# brush.net
KiCad netlist of a schematic drawn in EAGLE
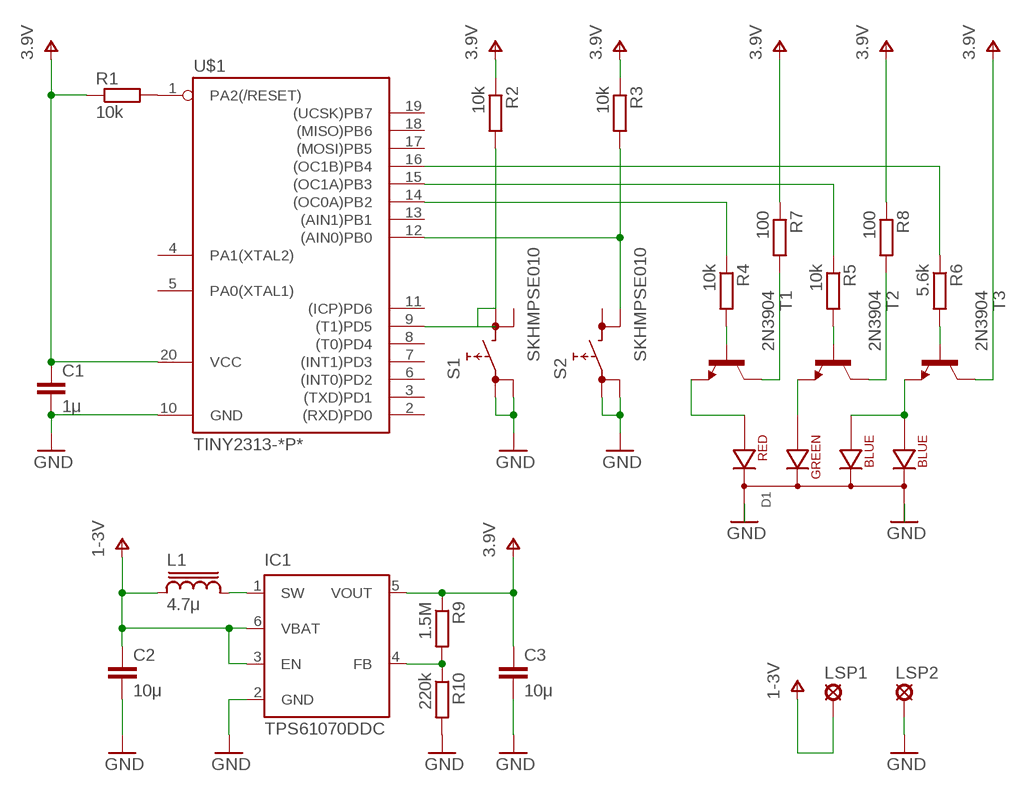
[diagram p0: schematic, sheet 1]

(export (version "E")
  (design (tool "Eeschema 10.0.6"))
  (components
    (comp (ref "C1")
      (value "1μ")
      (footprint "eagle-import:C1206")
      (libsource (lib "eagle-import") (part "C-EUC1206"))
    )
    (comp (ref "C2")
      (value "10μ")
      (footprint "eagle-import:C1206")
      (libsource (lib "eagle-import") (part "C-EUC1206"))
    )
    (comp (ref "C3")
      (value "10μ")
      (footprint "eagle-import:C1206")
      (libsource (lib "eagle-import") (part "C-EUC1206"))
    )
    (comp (ref "D1")
      (value "LED-RGB-CC-THRUDIFFUSE")
      (footprint "eagle-import:LED-RGB-THRU")
      (libsource (lib "eagle-import") (part "LED-RGB-CC-THRUDIFFUSE"))
    )
    (comp (ref "IC1")
      (value "TPS61070DDC")
      (footprint "eagle-import:TSOT23-6_DDC")
      (fields (field (name "MPN") "TPS61070DDCR"))
      (libsource (lib "eagle-import") (part "TPS6107DDC0"))
    )
    (comp (ref "L1")
      (value "4.7μ")
      (footprint "eagle-import:CR43")
      (libsource (lib "eagle-import") (part "CR43"))
    )
    (comp (ref "LSP1")
      (value "LSP10")
      (footprint "eagle-import:LSP10")
      (libsource (lib "eagle-import") (part "LSP10"))
    )
    (comp (ref "LSP2")
      (value "LSP10")
      (footprint "eagle-import:LSP10")
      (libsource (lib "eagle-import") (part "LSP10"))
    )
    (comp (ref "R1")
      (value "10k")
      (footprint "eagle-import:R1206")
      (libsource (lib "eagle-import") (part "R-EU_R1206"))
    )
    (comp (ref "R2")
      (value "10k")
      (footprint "eagle-import:R1206")
      (libsource (lib "eagle-import") (part "R-EU_R1206"))
    )
    (comp (ref "R3")
      (value "10k")
      (footprint "eagle-import:R1206")
      (libsource (lib "eagle-import") (part "R-EU_R1206"))
    )
    (comp (ref "R4")
      (value "10k")
      (footprint "eagle-import:R1206")
      (libsource (lib "eagle-import") (part "R-EU_R1206"))
    )
    (comp (ref "R5")
      (value "10k")
      (footprint "eagle-import:R1206")
      (libsource (lib "eagle-import") (part "R-EU_R1206"))
    )
    (comp (ref "R6")
      (value "5.6k")
      (footprint "eagle-import:R1206")
      (libsource (lib "eagle-import") (part "R-EU_R1206"))
    )
    (comp (ref "R7")
      (value "100")
      (footprint "eagle-import:R1206")
      (libsource (lib "eagle-import") (part "R-EU_R1206"))
    )
    (comp (ref "R8")
      (value "100")
      (footprint "eagle-import:R1206")
      (libsource (lib "eagle-import") (part "R-EU_R1206"))
    )
    (comp (ref "R9")
      (value "1.5M")
      (footprint "eagle-import:R1206")
      (libsource (lib "eagle-import") (part "R-EU_R1206"))
    )
    (comp (ref "R10")
      (value "220k")
      (footprint "eagle-import:R1206")
      (libsource (lib "eagle-import") (part "R-EU_R1206"))
    )
    (comp (ref "S1")
      (value "SKHMPSE010")
      (footprint "eagle-import:SKHMPXE010")
      (libsource (lib "eagle-import") (part "SKHMPE010S"))
    )
    (comp (ref "S2")
      (value "SKHMPSE010")
      (footprint "eagle-import:SKHMPXE010")
      (libsource (lib "eagle-import") (part "SKHMPE010S"))
    )
    (comp (ref "T1")
      (value "2N3904")
      (footprint "eagle-import:TO92")
      (libsource (lib "eagle-import") (part "2N3904"))
    )
    (comp (ref "T2")
      (value "2N3904")
      (footprint "eagle-import:TO92")
      (libsource (lib "eagle-import") (part "2N3904"))
    )
    (comp (ref "T3")
      (value "2N3904")
      (footprint "eagle-import:TO92")
      (libsource (lib "eagle-import") (part "2N3904"))
    )
    (comp (ref "U$1")
      (value "TINY2313-*P*")
      (footprint "eagle-import:DIL20")
      (libsource (lib "eagle-import") (part "TINY2313-P"))
    )
  )
  (nets
    (net (code "1") (name "1-3V") (class "Default")
      (node (ref "C1") (pin "1") (pinfunction "1_1") (pintype "passive"))
      (node (ref "C2") (pin "1") (pinfunction "1_1") (pintype "passive"))
      (node (ref "C3") (pin "1") (pinfunction "1_1") (pintype "passive"))
      (node (ref "IC1") (pin "3") (pinfunction "EN_3") (pintype "input"))
      (node (ref "IC1") (pin "5") (pinfunction "VOUT_5") (pintype "passive"))
      (node (ref "IC1") (pin "6") (pinfunction "VBAT_6") (pintype "input"))
      (node (ref "L1") (pin "1") (pinfunction "1_1") (pintype "passive"))
      (node (ref "LSP1") (pin "MP") (pinfunction "MP_MP") (pintype "passive"))
      (node (ref "R1") (pin "1") (pinfunction "1_1") (pintype "passive"))
      (node (ref "R2") (pin "1") (pinfunction "1_1") (pintype "passive"))
      (node (ref "R3") (pin "1") (pinfunction "1_1") (pintype "passive"))
      (node (ref "R7") (pin "1") (pinfunction "1_1") (pintype "passive"))
      (node (ref "R8") (pin "1") (pinfunction "1_1") (pintype "passive"))
      (node (ref "R9") (pin "1") (pinfunction "1_1") (pintype "passive"))
      (node (ref "T3") (pin "1") (pinfunction "C_1") (pintype "passive"))
      (node (ref "U$1") (pin "20") (pinfunction "VCC_20") (pintype "power_in"))
    )
    (net (code "2") (name "GND") (class "Default")
      (node (ref "C1") (pin "2") (pinfunction "2_2") (pintype "passive"))
      (node (ref "C2") (pin "2") (pinfunction "2_2") (pintype "passive"))
      (node (ref "C3") (pin "2") (pinfunction "2_2") (pintype "passive"))
      (node (ref "D1") (pin "CATHODE1") (pinfunction "CATHODE1_CATHODE1") (pintype "bidirectional"))
      (node (ref "D1") (pin "CATHODE2") (pinfunction "CATHODE2_CATHODE2") (pintype "bidirectional"))
      (node (ref "IC1") (pin "2") (pinfunction "GND_2") (pintype "power_in"))
      (node (ref "LSP2") (pin "MP") (pinfunction "MP_MP") (pintype "passive"))
      (node (ref "R10") (pin "2") (pinfunction "2_2") (pintype "passive"))
      (node (ref "S1") (pin "1") (pinfunction "1.1_1") (pintype "passive"))
      (node (ref "S1") (pin "2") (pinfunction "1.2_2") (pintype "passive"))
      (node (ref "S2") (pin "1") (pinfunction "1.1_1") (pintype "passive"))
      (node (ref "S2") (pin "2") (pinfunction "1.2_2") (pintype "passive"))
      (node (ref "U$1") (pin "10") (pinfunction "GND_10") (pintype "power_in"))
    )
    (net (code "3") (name "Net-(IC1-FB)") (class "Default")
      (node (ref "IC1") (pin "4") (pinfunction "FB_4") (pintype "input"))
      (node (ref "R10") (pin "1") (pinfunction "1_1") (pintype "passive"))
      (node (ref "R9") (pin "2") (pinfunction "2_2") (pintype "passive"))
    )
    (net (code "4") (name "Net-(IC1-SW)") (class "Default")
      (node (ref "IC1") (pin "1") (pinfunction "SW_1") (pintype "input"))
      (node (ref "L1") (pin "2") (pinfunction "2_2") (pintype "passive"))
    )
    (net (code "5") (name "Net-(S1-2.1)") (class "Default")
      (node (ref "R2") (pin "2") (pinfunction "2_2") (pintype "passive"))
      (node (ref "S1") (pin "3") (pinfunction "2.1_3") (pintype "passive"))
      (node (ref "U$1") (pin "9") (pinfunction "(T1)PD5_9") (pintype "bidirectional"))
    )
    (net (code "6") (name "Net-(S2-2.2)") (class "Default")
      (node (ref "R3") (pin "2") (pinfunction "2_2") (pintype "passive"))
      (node (ref "S2") (pin "4") (pinfunction "2.2_4") (pintype "passive"))
      (node (ref "U$1") (pin "12") (pinfunction "(AIN0)PB0_12") (pintype "bidirectional"))
    )
    (net (code "7") (name "Net-(T1-B)") (class "Default")
      (node (ref "R4") (pin "2") (pinfunction "2_2") (pintype "passive"))
      (node (ref "T1") (pin "2") (pinfunction "B_2") (pintype "passive"))
    )
    (net (code "8") (name "Net-(T1-C)") (class "Default")
      (node (ref "R7") (pin "2") (pinfunction "2_2") (pintype "passive"))
      (node (ref "T1") (pin "1") (pinfunction "C_1") (pintype "passive"))
    )
    (net (code "9") (name "Net-(T1-E)") (class "Default")
      (node (ref "D1") (pin "RED") (pinfunction "RED_RED") (pintype "bidirectional"))
      (node (ref "T1") (pin "3") (pinfunction "E_3") (pintype "passive"))
    )
    (net (code "10") (name "Net-(T2-B)") (class "Default")
      (node (ref "R5") (pin "2") (pinfunction "2_2") (pintype "passive"))
      (node (ref "T2") (pin "2") (pinfunction "B_2") (pintype "passive"))
    )
    (net (code "11") (name "Net-(T2-C)") (class "Default")
      (node (ref "R8") (pin "2") (pinfunction "2_2") (pintype "passive"))
      (node (ref "T2") (pin "1") (pinfunction "C_1") (pintype "passive"))
    )
    (net (code "12") (name "Net-(T2-E)") (class "Default")
      (node (ref "D1") (pin "GREEN") (pinfunction "GREEN_GREEN") (pintype "bidirectional"))
      (node (ref "T2") (pin "3") (pinfunction "E_3") (pintype "passive"))
    )
    (net (code "13") (name "Net-(T3-B)") (class "Default")
      (node (ref "R6") (pin "2") (pinfunction "2_2") (pintype "passive"))
      (node (ref "T3") (pin "2") (pinfunction "B_2") (pintype "passive"))
    )
    (net (code "14") (name "Net-(T3-E)") (class "Default")
      (node (ref "D1") (pin "BLUE1") (pinfunction "BLUE1_BLUE1") (pintype "bidirectional"))
      (node (ref "D1") (pin "BLUE2") (pinfunction "BLUE2_BLUE2") (pintype "bidirectional"))
      (node (ref "T3") (pin "3") (pinfunction "E_3") (pintype "passive"))
    )
    (net (code "15") (name "Net-(U$1-(OC0A)PB2)") (class "Default")
      (node (ref "R4") (pin "1") (pinfunction "1_1") (pintype "passive"))
      (node (ref "U$1") (pin "14") (pinfunction "(OC0A)PB2_14") (pintype "bidirectional"))
    )
    (net (code "16") (name "Net-(U$1-(OC1A)PB3)") (class "Default")
      (node (ref "R5") (pin "1") (pinfunction "1_1") (pintype "passive"))
      (node (ref "U$1") (pin "15") (pinfunction "(OC1A)PB3_15") (pintype "bidirectional"))
    )
    (net (code "17") (name "Net-(U$1-(OC1B)PB4)") (class "Default")
      (node (ref "R6") (pin "1") (pinfunction "1_1") (pintype "passive"))
      (node (ref "U$1") (pin "16") (pinfunction "(OC1B)PB4_16") (pintype "bidirectional"))
    )
    (net (code "18") (name "Net-(U$1-PA2({slash}RESET))") (class "Default")
      (node (ref "R1") (pin "2") (pinfunction "2_2") (pintype "passive"))
      (node (ref "U$1") (pin "1") (pinfunction "PA2(/RESET)_1") (pintype "input"))
    )
    (net (code "19") (name "unconnected-(S1-2.2-Pad4)") (class "Default")
      (node (ref "S1") (pin "4") (pinfunction "2.2_4") (pintype "passive"))
    )
    (net (code "20") (name "unconnected-(S2-2.1-Pad3)") (class "Default")
      (node (ref "S2") (pin "3") (pinfunction "2.1_3") (pintype "passive"))
    )
    (net (code "21") (name "unconnected-(U$1-(AIN1)PB1-Pad13)") (class "Default")
      (node (ref "U$1") (pin "13") (pinfunction "(AIN1)PB1_13") (pintype "bidirectional"))
    )
    (net (code "22") (name "unconnected-(U$1-(ICP)PD6-Pad11)") (class "Default")
      (node (ref "U$1") (pin "11") (pinfunction "(ICP)PD6_11") (pintype "bidirectional"))
    )
    (net (code "23") (name "unconnected-(U$1-(INT0)PD2-Pad6)") (class "Default")
      (node (ref "U$1") (pin "6") (pinfunction "(INT0)PD2_6") (pintype "bidirectional"))
    )
    (net (code "24") (name "unconnected-(U$1-(INT1)PD3-Pad7)") (class "Default")
      (node (ref "U$1") (pin "7") (pinfunction "(INT1)PD3_7") (pintype "bidirectional"))
    )
    (net (code "25") (name "unconnected-(U$1-(MISO)PB6-Pad18)") (class "Default")
      (node (ref "U$1") (pin "18") (pinfunction "(MISO)PB6_18") (pintype "bidirectional"))
    )
    (net (code "26") (name "unconnected-(U$1-(MOSI)PB5-Pad17)") (class "Default")
      (node (ref "U$1") (pin "17") (pinfunction "(MOSI)PB5_17") (pintype "bidirectional"))
    )
    (net (code "27") (name "unconnected-(U$1-(RXD)PD0-Pad2)") (class "Default")
      (node (ref "U$1") (pin "2") (pinfunction "(RXD)PD0_2") (pintype "bidirectional"))
    )
    (net (code "28") (name "unconnected-(U$1-(T0)PD4-Pad8)") (class "Default")
      (node (ref "U$1") (pin "8") (pinfunction "(T0)PD4_8") (pintype "bidirectional"))
    )
    (net (code "29") (name "unconnected-(U$1-(TXD)PD1-Pad3)") (class "Default")
      (node (ref "U$1") (pin "3") (pinfunction "(TXD)PD1_3") (pintype "bidirectional"))
    )
    (net (code "30") (name "unconnected-(U$1-(UCSK)PB7-Pad19)") (class "Default")
      (node (ref "U$1") (pin "19") (pinfunction "(UCSK)PB7_19") (pintype "bidirectional"))
    )
    (net (code "31") (name "unconnected-(U$1-PA0(XTAL1)-Pad5)") (class "Default")
      (node (ref "U$1") (pin "5") (pinfunction "PA0(XTAL1)_5") (pintype "bidirectional"))
    )
    (net (code "32") (name "unconnected-(U$1-PA1(XTAL2)-Pad4)") (class "Default")
      (node (ref "U$1") (pin "4") (pinfunction "PA1(XTAL2)_4") (pintype "bidirectional"))
    )
  )
)
